# rotary-encoders.net
KiCad netlist of a schematic drawn in EAGLE
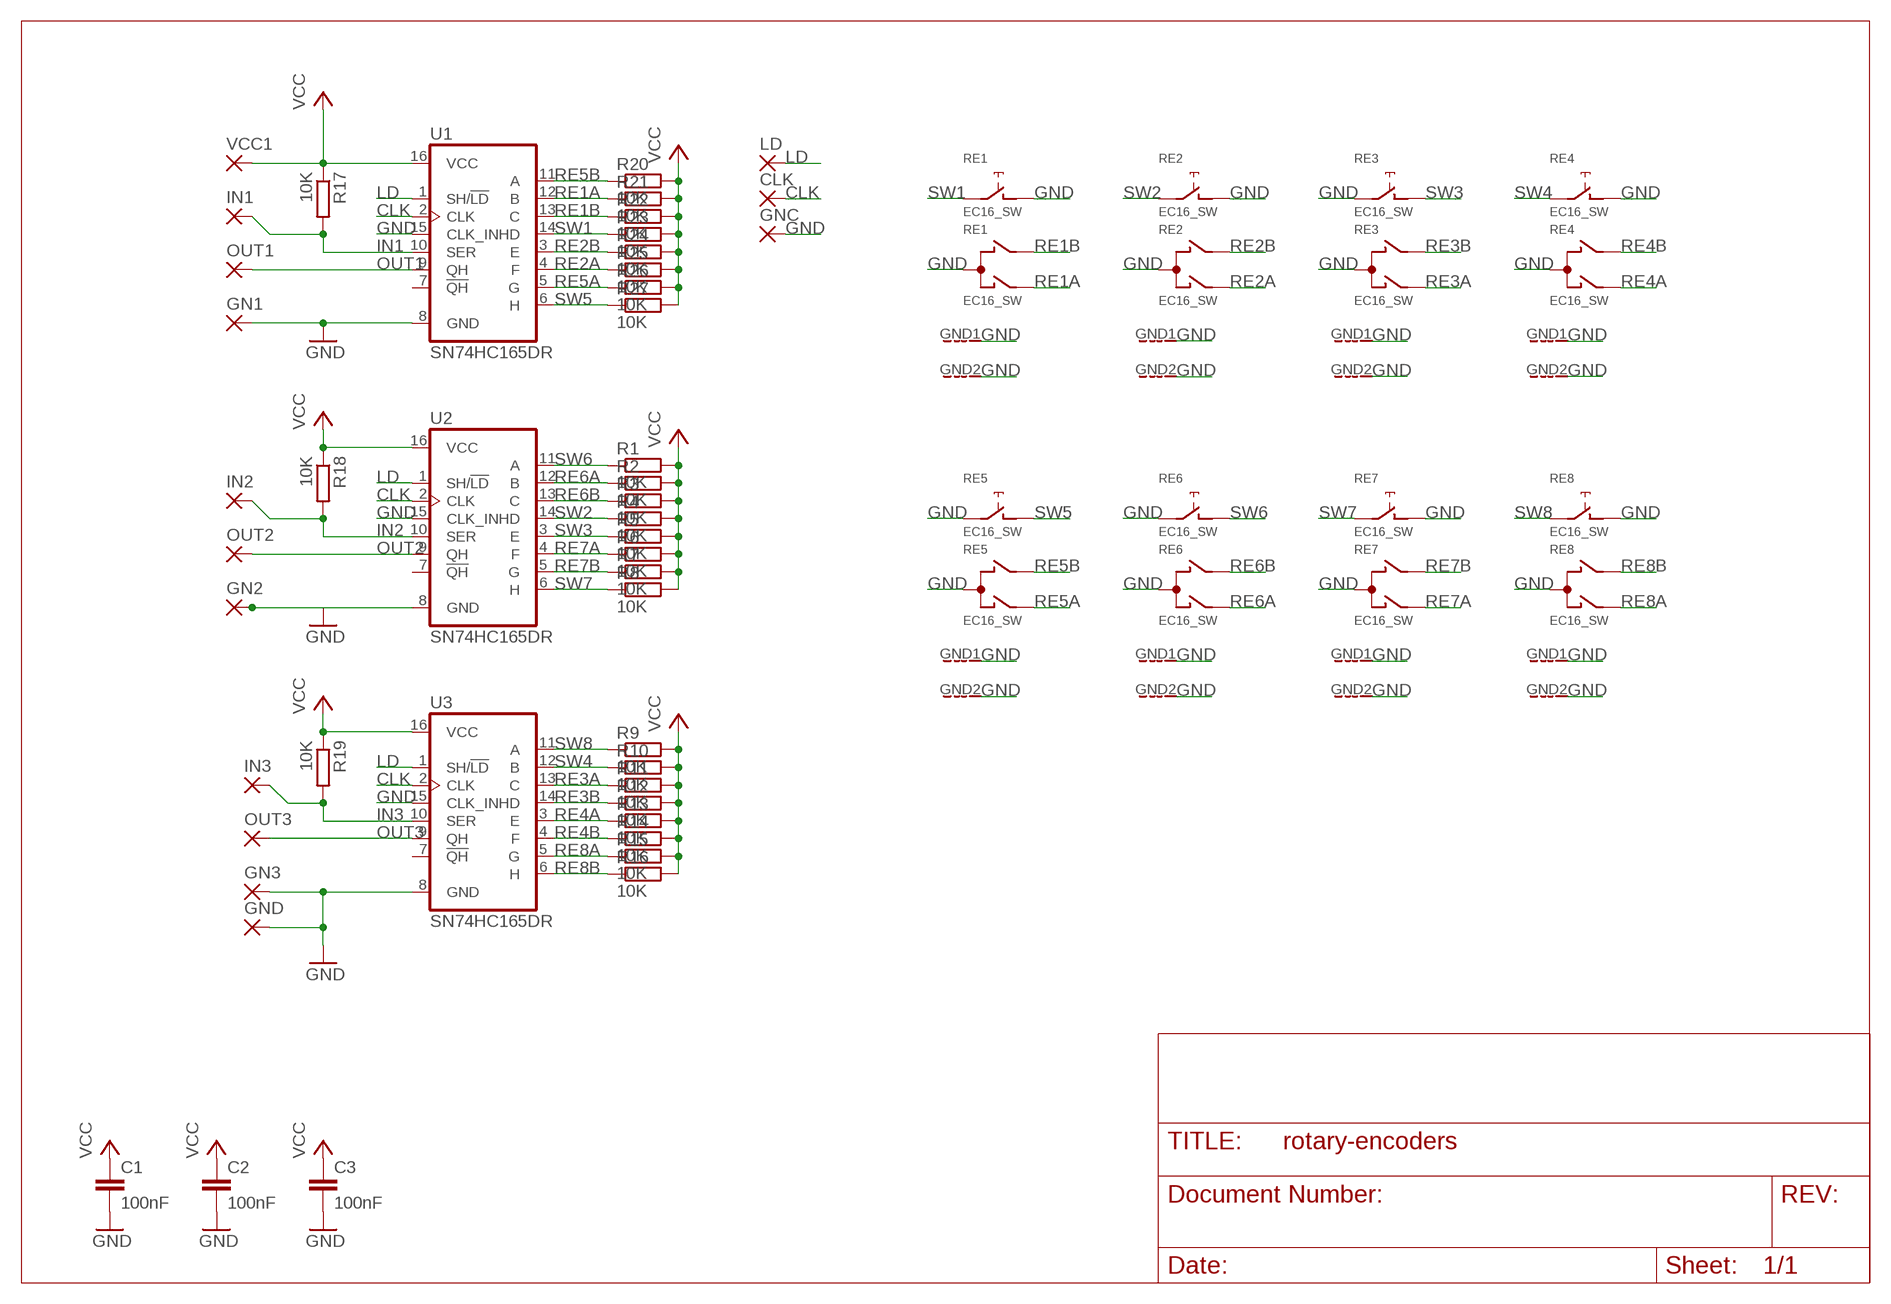
[diagram p0: schematic, sheet 1]

(export (version "E")
  (design (tool "Eeschema 10.0.6"))
  (components
    (comp (ref "C1")
      (value "100nF")
      (footprint "eagle-import:C0805")
      (libsource (lib "eagle-import") (part "C-EUC0805"))
    )
    (comp (ref "C2")
      (value "100nF")
      (footprint "eagle-import:C0805")
      (libsource (lib "eagle-import") (part "C-EUC0805"))
    )
    (comp (ref "C3")
      (value "100nF")
      (footprint "eagle-import:C0805")
      (libsource (lib "eagle-import") (part "C-EUC0805"))
    )
    (comp (ref "CLK")
      (value "1,6/0,9")
      (footprint "eagle-import:1,6_0,9")
      (libsource (lib "eagle-import") (part "1,6/0,9"))
    )
    (comp (ref "GN1")
      (value "1,6/0,9")
      (footprint "eagle-import:1,6_0,9")
      (libsource (lib "eagle-import") (part "1,6/0,9"))
    )
    (comp (ref "GN2")
      (value "1,6/0,9")
      (footprint "eagle-import:1,6_0,9")
      (libsource (lib "eagle-import") (part "1,6/0,9"))
    )
    (comp (ref "GN3")
      (value "1,6/0,9")
      (footprint "eagle-import:1,6_0,9")
      (libsource (lib "eagle-import") (part "1,6/0,9"))
    )
    (comp (ref "GNC")
      (value "1,6/0,9")
      (footprint "eagle-import:1,6_0,9")
      (libsource (lib "eagle-import") (part "1,6/0,9"))
    )
    (comp (ref "GND")
      (value "1,6/0,9")
      (footprint "eagle-import:1,6_0,9")
      (libsource (lib "eagle-import") (part "1,6/0,9"))
    )
    (comp (ref "IN1")
      (value "1,6/0,9")
      (footprint "eagle-import:1,6_0,9")
      (libsource (lib "eagle-import") (part "1,6/0,9"))
    )
    (comp (ref "IN2")
      (value "1,6/0,9")
      (footprint "eagle-import:1,6_0,9")
      (libsource (lib "eagle-import") (part "1,6/0,9"))
    )
    (comp (ref "IN3")
      (value "1,6/0,9")
      (footprint "eagle-import:1,6_0,9")
      (libsource (lib "eagle-import") (part "1,6/0,9"))
    )
    (comp (ref "LD")
      (value "1,6/0,9")
      (footprint "eagle-import:1,6_0,9")
      (libsource (lib "eagle-import") (part "1,6/0,9"))
    )
    (comp (ref "OUT1")
      (value "1,6/0,9")
      (footprint "eagle-import:1,6_0,9")
      (libsource (lib "eagle-import") (part "1,6/0,9"))
    )
    (comp (ref "OUT2")
      (value "1,6/0,9")
      (footprint "eagle-import:1,6_0,9")
      (libsource (lib "eagle-import") (part "1,6/0,9"))
    )
    (comp (ref "OUT3")
      (value "1,6/0,9")
      (footprint "eagle-import:1,6_0,9")
      (libsource (lib "eagle-import") (part "1,6/0,9"))
    )
    (comp (ref "R1")
      (value "10K")
      (footprint "eagle-import:R0805")
      (libsource (lib "eagle-import") (part "R-EU_R0805"))
    )
    (comp (ref "R2")
      (value "10K")
      (footprint "eagle-import:R0805")
      (libsource (lib "eagle-import") (part "R-EU_R0805"))
    )
    (comp (ref "R3")
      (value "10K")
      (footprint "eagle-import:R0805")
      (libsource (lib "eagle-import") (part "R-EU_R0805"))
    )
    (comp (ref "R4")
      (value "10K")
      (footprint "eagle-import:R0805")
      (libsource (lib "eagle-import") (part "R-EU_R0805"))
    )
    (comp (ref "R5")
      (value "10K")
      (footprint "eagle-import:R0805")
      (libsource (lib "eagle-import") (part "R-EU_R0805"))
    )
    (comp (ref "R6")
      (value "10K")
      (footprint "eagle-import:R0805")
      (libsource (lib "eagle-import") (part "R-EU_R0805"))
    )
    (comp (ref "R7")
      (value "10K")
      (footprint "eagle-import:R0805")
      (libsource (lib "eagle-import") (part "R-EU_R0805"))
    )
    (comp (ref "R8")
      (value "10K")
      (footprint "eagle-import:R0805")
      (libsource (lib "eagle-import") (part "R-EU_R0805"))
    )
    (comp (ref "R9")
      (value "10K")
      (footprint "eagle-import:R0805")
      (libsource (lib "eagle-import") (part "R-EU_R0805"))
    )
    (comp (ref "R10")
      (value "10K")
      (footprint "eagle-import:R0805")
      (libsource (lib "eagle-import") (part "R-EU_R0805"))
    )
    (comp (ref "R11")
      (value "10K")
      (footprint "eagle-import:R0805")
      (libsource (lib "eagle-import") (part "R-EU_R0805"))
    )
    (comp (ref "R12")
      (value "10K")
      (footprint "eagle-import:R0805")
      (libsource (lib "eagle-import") (part "R-EU_R0805"))
    )
    (comp (ref "R13")
      (value "10K")
      (footprint "eagle-import:R0805")
      (libsource (lib "eagle-import") (part "R-EU_R0805"))
    )
    (comp (ref "R14")
      (value "10K")
      (footprint "eagle-import:R0805")
      (libsource (lib "eagle-import") (part "R-EU_R0805"))
    )
    (comp (ref "R15")
      (value "10K")
      (footprint "eagle-import:R0805")
      (libsource (lib "eagle-import") (part "R-EU_R0805"))
    )
    (comp (ref "R16")
      (value "10K")
      (footprint "eagle-import:R0805")
      (libsource (lib "eagle-import") (part "R-EU_R0805"))
    )
    (comp (ref "R17")
      (value "10K")
      (footprint "eagle-import:R0805")
      (libsource (lib "eagle-import") (part "R-EU_R0805"))
    )
    (comp (ref "R18")
      (value "10K")
      (footprint "eagle-import:R0805")
      (libsource (lib "eagle-import") (part "R-EU_R0805"))
    )
    (comp (ref "R19")
      (value "10K")
      (footprint "eagle-import:R0805")
      (libsource (lib "eagle-import") (part "R-EU_R0805"))
    )
    (comp (ref "R20")
      (value "10K")
      (footprint "eagle-import:R0805")
      (libsource (lib "eagle-import") (part "R-EU_R0805"))
    )
    (comp (ref "R21")
      (value "10K")
      (footprint "eagle-import:R0805")
      (libsource (lib "eagle-import") (part "R-EU_R0805"))
    )
    (comp (ref "R22")
      (value "10K")
      (footprint "eagle-import:R0805")
      (libsource (lib "eagle-import") (part "R-EU_R0805"))
    )
    (comp (ref "R23")
      (value "10K")
      (footprint "eagle-import:R0805")
      (libsource (lib "eagle-import") (part "R-EU_R0805"))
    )
    (comp (ref "R24")
      (value "10K")
      (footprint "eagle-import:R0805")
      (libsource (lib "eagle-import") (part "R-EU_R0805"))
    )
    (comp (ref "R25")
      (value "10K")
      (footprint "eagle-import:R0805")
      (libsource (lib "eagle-import") (part "R-EU_R0805"))
    )
    (comp (ref "R26")
      (value "10K")
      (footprint "eagle-import:R0805")
      (libsource (lib "eagle-import") (part "R-EU_R0805"))
    )
    (comp (ref "R27")
      (value "10K")
      (footprint "eagle-import:R0805")
      (libsource (lib "eagle-import") (part "R-EU_R0805"))
    )
    (comp (ref "RE1")
      (value "EC16_SW")
      (footprint "eagle-import:EC16_SW")
      (libsource (lib "eagle-import") (part "EC16_SW"))
    )
    (comp (ref "RE2")
      (value "EC16_SW")
      (footprint "eagle-import:EC16_SW")
      (libsource (lib "eagle-import") (part "EC16_SW"))
    )
    (comp (ref "RE3")
      (value "EC16_SW")
      (footprint "eagle-import:EC16_SW")
      (libsource (lib "eagle-import") (part "EC16_SW"))
    )
    (comp (ref "RE4")
      (value "EC16_SW")
      (footprint "eagle-import:EC16_SW")
      (libsource (lib "eagle-import") (part "EC16_SW"))
    )
    (comp (ref "RE5")
      (value "EC16_SW")
      (footprint "eagle-import:EC16_SW")
      (libsource (lib "eagle-import") (part "EC16_SW"))
    )
    (comp (ref "RE6")
      (value "EC16_SW")
      (footprint "eagle-import:EC16_SW")
      (libsource (lib "eagle-import") (part "EC16_SW"))
    )
    (comp (ref "RE7")
      (value "EC16_SW")
      (footprint "eagle-import:EC16_SW")
      (libsource (lib "eagle-import") (part "EC16_SW"))
    )
    (comp (ref "RE8")
      (value "EC16_SW")
      (footprint "eagle-import:EC16_SW")
      (libsource (lib "eagle-import") (part "EC16_SW"))
    )
    (comp (ref "U1")
      (value "SN74HC165DR")
      (footprint "eagle-import:SO16")
      (libsource (lib "eagle-import") (part "74165DHC"))
    )
    (comp (ref "U2")
      (value "SN74HC165DR")
      (footprint "eagle-import:SO16")
      (libsource (lib "eagle-import") (part "74165DHC"))
    )
    (comp (ref "U3")
      (value "SN74HC165DR")
      (footprint "eagle-import:SO16")
      (libsource (lib "eagle-import") (part "74165DHC"))
    )
    (comp (ref "VCC1")
      (value "1,6/0,9")
      (footprint "eagle-import:1,6_0,9")
      (libsource (lib "eagle-import") (part "1,6/0,9"))
    )
  )
  (nets
    (net (code "1") (name "/CLK") (class "Default")
      (node (ref "CLK") (pin "1") (pinfunction "P_1") (pintype "passive"))
      (node (ref "U1") (pin "2") (pinfunction "CLK_2") (pintype "input"))
      (node (ref "U2") (pin "2") (pinfunction "CLK_2") (pintype "input"))
      (node (ref "U3") (pin "2") (pinfunction "CLK_2") (pintype "input"))
    )
    (net (code "2") (name "/IN1") (class "Default")
      (node (ref "IN1") (pin "1") (pinfunction "P_1") (pintype "passive"))
      (node (ref "R17") (pin "2") (pinfunction "2_2") (pintype "passive"))
      (node (ref "U1") (pin "10") (pinfunction "SER_10") (pintype "input"))
    )
    (net (code "3") (name "/IN2") (class "Default")
      (node (ref "IN2") (pin "1") (pinfunction "P_1") (pintype "passive"))
      (node (ref "R18") (pin "2") (pinfunction "2_2") (pintype "passive"))
      (node (ref "U2") (pin "10") (pinfunction "SER_10") (pintype "input"))
    )
    (net (code "4") (name "/IN3") (class "Default")
      (node (ref "IN3") (pin "1") (pinfunction "P_1") (pintype "passive"))
      (node (ref "R19") (pin "2") (pinfunction "2_2") (pintype "passive"))
      (node (ref "U3") (pin "10") (pinfunction "SER_10") (pintype "input"))
    )
    (net (code "5") (name "/LD") (class "Default")
      (node (ref "LD") (pin "1") (pinfunction "P_1") (pintype "passive"))
      (node (ref "U1") (pin "1") (pinfunction "SH/~{LD}_1") (pintype "input"))
      (node (ref "U2") (pin "1") (pinfunction "SH/~{LD}_1") (pintype "input"))
      (node (ref "U3") (pin "1") (pinfunction "SH/~{LD}_1") (pintype "input"))
    )
    (net (code "6") (name "/OUT1") (class "Default")
      (node (ref "OUT1") (pin "1") (pinfunction "P_1") (pintype "passive"))
      (node (ref "U1") (pin "9") (pinfunction "QH_9") (pintype "tri_state"))
    )
    (net (code "7") (name "/OUT2") (class "Default")
      (node (ref "OUT2") (pin "1") (pinfunction "P_1") (pintype "passive"))
      (node (ref "U2") (pin "9") (pinfunction "QH_9") (pintype "tri_state"))
    )
    (net (code "8") (name "/OUT3") (class "Default")
      (node (ref "OUT3") (pin "1") (pinfunction "P_1") (pintype "passive"))
      (node (ref "U3") (pin "9") (pinfunction "QH_9") (pintype "tri_state"))
    )
    (net (code "9") (name "/RE1A") (class "Default")
      (node (ref "R21") (pin "1") (pinfunction "1_1") (pintype "passive"))
      (node (ref "RE1") (pin "A") (pinfunction "A_A") (pintype "passive"))
      (node (ref "U1") (pin "12") (pinfunction "B_12") (pintype "tri_state"))
    )
    (net (code "10") (name "/RE1B") (class "Default")
      (node (ref "R22") (pin "1") (pinfunction "1_1") (pintype "passive"))
      (node (ref "RE1") (pin "B") (pinfunction "B_B") (pintype "passive"))
      (node (ref "U1") (pin "13") (pinfunction "C_13") (pintype "tri_state"))
    )
    (net (code "11") (name "/RE2A") (class "Default")
      (node (ref "R25") (pin "1") (pinfunction "1_1") (pintype "passive"))
      (node (ref "RE2") (pin "A") (pinfunction "A_A") (pintype "passive"))
      (node (ref "U1") (pin "4") (pinfunction "F_4") (pintype "tri_state"))
    )
    (net (code "12") (name "/RE2B") (class "Default")
      (node (ref "R24") (pin "1") (pinfunction "1_1") (pintype "passive"))
      (node (ref "RE2") (pin "B") (pinfunction "B_B") (pintype "passive"))
      (node (ref "U1") (pin "3") (pinfunction "E_3") (pintype "tri_state"))
    )
    (net (code "13") (name "/RE3A") (class "Default")
      (node (ref "R11") (pin "1") (pinfunction "1_1") (pintype "passive"))
      (node (ref "RE3") (pin "A") (pinfunction "A_A") (pintype "passive"))
      (node (ref "U3") (pin "13") (pinfunction "C_13") (pintype "tri_state"))
    )
    (net (code "14") (name "/RE3B") (class "Default")
      (node (ref "R12") (pin "1") (pinfunction "1_1") (pintype "passive"))
      (node (ref "RE3") (pin "B") (pinfunction "B_B") (pintype "passive"))
      (node (ref "U3") (pin "14") (pinfunction "D_14") (pintype "tri_state"))
    )
    (net (code "15") (name "/RE4A") (class "Default")
      (node (ref "R13") (pin "1") (pinfunction "1_1") (pintype "passive"))
      (node (ref "RE4") (pin "A") (pinfunction "A_A") (pintype "passive"))
      (node (ref "U3") (pin "3") (pinfunction "E_3") (pintype "tri_state"))
    )
    (net (code "16") (name "/RE4B") (class "Default")
      (node (ref "R14") (pin "1") (pinfunction "1_1") (pintype "passive"))
      (node (ref "RE4") (pin "B") (pinfunction "B_B") (pintype "passive"))
      (node (ref "U3") (pin "4") (pinfunction "F_4") (pintype "tri_state"))
    )
    (net (code "17") (name "/RE5A") (class "Default")
      (node (ref "R26") (pin "1") (pinfunction "1_1") (pintype "passive"))
      (node (ref "RE5") (pin "A") (pinfunction "A_A") (pintype "passive"))
      (node (ref "U1") (pin "5") (pinfunction "G_5") (pintype "tri_state"))
    )
    (net (code "18") (name "/RE5B") (class "Default")
      (node (ref "R20") (pin "1") (pinfunction "1_1") (pintype "passive"))
      (node (ref "RE5") (pin "B") (pinfunction "B_B") (pintype "passive"))
      (node (ref "U1") (pin "11") (pinfunction "A_11") (pintype "tri_state"))
    )
    (net (code "19") (name "/RE6A") (class "Default")
      (node (ref "R2") (pin "1") (pinfunction "1_1") (pintype "passive"))
      (node (ref "RE6") (pin "A") (pinfunction "A_A") (pintype "passive"))
      (node (ref "U2") (pin "12") (pinfunction "B_12") (pintype "tri_state"))
    )
    (net (code "20") (name "/RE6B") (class "Default")
      (node (ref "R3") (pin "1") (pinfunction "1_1") (pintype "passive"))
      (node (ref "RE6") (pin "B") (pinfunction "B_B") (pintype "passive"))
      (node (ref "U2") (pin "13") (pinfunction "C_13") (pintype "tri_state"))
    )
    (net (code "21") (name "/RE7A") (class "Default")
      (node (ref "R6") (pin "1") (pinfunction "1_1") (pintype "passive"))
      (node (ref "RE7") (pin "A") (pinfunction "A_A") (pintype "passive"))
      (node (ref "U2") (pin "4") (pinfunction "F_4") (pintype "tri_state"))
    )
    (net (code "22") (name "/RE7B") (class "Default")
      (node (ref "R7") (pin "1") (pinfunction "1_1") (pintype "passive"))
      (node (ref "RE7") (pin "B") (pinfunction "B_B") (pintype "passive"))
      (node (ref "U2") (pin "5") (pinfunction "G_5") (pintype "tri_state"))
    )
    (net (code "23") (name "/RE8A") (class "Default")
      (node (ref "R15") (pin "1") (pinfunction "1_1") (pintype "passive"))
      (node (ref "RE8") (pin "A") (pinfunction "A_A") (pintype "passive"))
      (node (ref "U3") (pin "5") (pinfunction "G_5") (pintype "tri_state"))
    )
    (net (code "24") (name "/RE8B") (class "Default")
      (node (ref "R16") (pin "1") (pinfunction "1_1") (pintype "passive"))
      (node (ref "RE8") (pin "B") (pinfunction "B_B") (pintype "passive"))
      (node (ref "U3") (pin "6") (pinfunction "H_6") (pintype "tri_state"))
    )
    (net (code "25") (name "/SW1") (class "Default")
      (node (ref "R23") (pin "1") (pinfunction "1_1") (pintype "passive"))
      (node (ref "RE1") (pin "E") (pinfunction "2_E") (pintype "passive"))
      (node (ref "U1") (pin "14") (pinfunction "D_14") (pintype "tri_state"))
    )
    (net (code "26") (name "/SW2") (class "Default")
      (node (ref "R4") (pin "1") (pinfunction "1_1") (pintype "passive"))
      (node (ref "RE2") (pin "E") (pinfunction "2_E") (pintype "passive"))
      (node (ref "U2") (pin "14") (pinfunction "D_14") (pintype "tri_state"))
    )
    (net (code "27") (name "/SW3") (class "Default")
      (node (ref "R5") (pin "1") (pinfunction "1_1") (pintype "passive"))
      (node (ref "RE3") (pin "D") (pinfunction "1_D") (pintype "passive"))
      (node (ref "U2") (pin "3") (pinfunction "E_3") (pintype "tri_state"))
    )
    (net (code "28") (name "/SW4") (class "Default")
      (node (ref "R10") (pin "1") (pinfunction "1_1") (pintype "passive"))
      (node (ref "RE4") (pin "E") (pinfunction "2_E") (pintype "passive"))
      (node (ref "U3") (pin "12") (pinfunction "B_12") (pintype "tri_state"))
    )
    (net (code "29") (name "/SW5") (class "Default")
      (node (ref "R27") (pin "1") (pinfunction "1_1") (pintype "passive"))
      (node (ref "RE5") (pin "D") (pinfunction "1_D") (pintype "passive"))
      (node (ref "U1") (pin "6") (pinfunction "H_6") (pintype "tri_state"))
    )
    (net (code "30") (name "/SW6") (class "Default")
      (node (ref "R1") (pin "1") (pinfunction "1_1") (pintype "passive"))
      (node (ref "RE6") (pin "D") (pinfunction "1_D") (pintype "passive"))
      (node (ref "U2") (pin "11") (pinfunction "A_11") (pintype "tri_state"))
    )
    (net (code "31") (name "/SW7") (class "Default")
      (node (ref "R8") (pin "1") (pinfunction "1_1") (pintype "passive"))
      (node (ref "RE7") (pin "E") (pinfunction "2_E") (pintype "passive"))
      (node (ref "U2") (pin "6") (pinfunction "H_6") (pintype "tri_state"))
    )
    (net (code "32") (name "/SW8") (class "Default")
      (node (ref "R9") (pin "1") (pinfunction "1_1") (pintype "passive"))
      (node (ref "RE8") (pin "E") (pinfunction "2_E") (pintype "passive"))
      (node (ref "U3") (pin "11") (pinfunction "A_11") (pintype "tri_state"))
    )
    (net (code "33") (name "GND") (class "Default")
      (node (ref "C1") (pin "2") (pinfunction "2_2") (pintype "passive"))
      (node (ref "C2") (pin "2") (pinfunction "2_2") (pintype "passive"))
      (node (ref "C3") (pin "2") (pinfunction "2_2") (pintype "passive"))
      (node (ref "GN1") (pin "1") (pinfunction "P_1") (pintype "passive"))
      (node (ref "GN2") (pin "1") (pinfunction "P_1") (pintype "passive"))
      (node (ref "GN3") (pin "1") (pinfunction "P_1") (pintype "passive"))
      (node (ref "GNC") (pin "1") (pinfunction "P_1") (pintype "passive"))
      (node (ref "GND") (pin "1") (pinfunction "P_1") (pintype "passive"))
      (node (ref "RE1") (pin "C") (pinfunction "C_C") (pintype "passive"))
      (node (ref "RE1") (pin "D") (pinfunction "1_D") (pintype "passive"))
      (node (ref "RE1") (pin "GND1") (pinfunction "G_GND1") (pintype "passive"))
      (node (ref "RE1") (pin "GND2") (pinfunction "G_GND2") (pintype "passive"))
      (node (ref "RE2") (pin "C") (pinfunction "C_C") (pintype "passive"))
      (node (ref "RE2") (pin "D") (pinfunction "1_D") (pintype "passive"))
      (node (ref "RE2") (pin "GND1") (pinfunction "G_GND1") (pintype "passive"))
      (node (ref "RE2") (pin "GND2") (pinfunction "G_GND2") (pintype "passive"))
      (node (ref "RE3") (pin "C") (pinfunction "C_C") (pintype "passive"))
      (node (ref "RE3") (pin "E") (pinfunction "2_E") (pintype "passive"))
      (node (ref "RE3") (pin "GND1") (pinfunction "G_GND1") (pintype "passive"))
      (node (ref "RE3") (pin "GND2") (pinfunction "G_GND2") (pintype "passive"))
      (node (ref "RE4") (pin "C") (pinfunction "C_C") (pintype "passive"))
      (node (ref "RE4") (pin "D") (pinfunction "1_D") (pintype "passive"))
      (node (ref "RE4") (pin "GND1") (pinfunction "G_GND1") (pintype "passive"))
      (node (ref "RE4") (pin "GND2") (pinfunction "G_GND2") (pintype "passive"))
      (node (ref "RE5") (pin "C") (pinfunction "C_C") (pintype "passive"))
      (node (ref "RE5") (pin "E") (pinfunction "2_E") (pintype "passive"))
      (node (ref "RE5") (pin "GND1") (pinfunction "G_GND1") (pintype "passive"))
      (node (ref "RE5") (pin "GND2") (pinfunction "G_GND2") (pintype "passive"))
      (node (ref "RE6") (pin "C") (pinfunction "C_C") (pintype "passive"))
      (node (ref "RE6") (pin "E") (pinfunction "2_E") (pintype "passive"))
      (node (ref "RE6") (pin "GND1") (pinfunction "G_GND1") (pintype "passive"))
      (node (ref "RE6") (pin "GND2") (pinfunction "G_GND2") (pintype "passive"))
      (node (ref "RE7") (pin "C") (pinfunction "C_C") (pintype "passive"))
      (node (ref "RE7") (pin "D") (pinfunction "1_D") (pintype "passive"))
      (node (ref "RE7") (pin "GND1") (pinfunction "G_GND1") (pintype "passive"))
      (node (ref "RE7") (pin "GND2") (pinfunction "G_GND2") (pintype "passive"))
      (node (ref "RE8") (pin "C") (pinfunction "C_C") (pintype "passive"))
      (node (ref "RE8") (pin "D") (pinfunction "1_D") (pintype "passive"))
      (node (ref "RE8") (pin "GND1") (pinfunction "G_GND1") (pintype "passive"))
      (node (ref "RE8") (pin "GND2") (pinfunction "G_GND2") (pintype "passive"))
      (node (ref "U1") (pin "15") (pinfunction "CLK_INH_15") (pintype "input"))
      (node (ref "U1") (pin "8") (pinfunction "GND_8") (pintype "power_in"))
      (node (ref "U2") (pin "15") (pinfunction "CLK_INH_15") (pintype "input"))
      (node (ref "U2") (pin "8") (pinfunction "GND_8") (pintype "power_in"))
      (node (ref "U3") (pin "15") (pinfunction "CLK_INH_15") (pintype "input"))
      (node (ref "U3") (pin "8") (pinfunction "GND_8") (pintype "power_in"))
    )
    (net (code "34") (name "VCC") (class "Default")
      (node (ref "C1") (pin "1") (pinfunction "1_1") (pintype "passive"))
      (node (ref "C2") (pin "1") (pinfunction "1_1") (pintype "passive"))
      (node (ref "C3") (pin "1") (pinfunction "1_1") (pintype "passive"))
      (node (ref "R1") (pin "2") (pinfunction "2_2") (pintype "passive"))
      (node (ref "R10") (pin "2") (pinfunction "2_2") (pintype "passive"))
      (node (ref "R11") (pin "2") (pinfunction "2_2") (pintype "passive"))
      (node (ref "R12") (pin "2") (pinfunction "2_2") (pintype "passive"))
      (node (ref "R13") (pin "2") (pinfunction "2_2") (pintype "passive"))
      (node (ref "R14") (pin "2") (pinfunction "2_2") (pintype "passive"))
      (node (ref "R15") (pin "2") (pinfunction "2_2") (pintype "passive"))
      (node (ref "R16") (pin "2") (pinfunction "2_2") (pintype "passive"))
      (node (ref "R17") (pin "1") (pinfunction "1_1") (pintype "passive"))
      (node (ref "R18") (pin "1") (pinfunction "1_1") (pintype "passive"))
      (node (ref "R19") (pin "1") (pinfunction "1_1") (pintype "passive"))
      (node (ref "R2") (pin "2") (pinfunction "2_2") (pintype "passive"))
      (node (ref "R20") (pin "2") (pinfunction "2_2") (pintype "passive"))
      (node (ref "R21") (pin "2") (pinfunction "2_2") (pintype "passive"))
      (node (ref "R22") (pin "2") (pinfunction "2_2") (pintype "passive"))
      (node (ref "R23") (pin "2") (pinfunction "2_2") (pintype "passive"))
      (node (ref "R24") (pin "2") (pinfunction "2_2") (pintype "passive"))
      (node (ref "R25") (pin "2") (pinfunction "2_2") (pintype "passive"))
      (node (ref "R26") (pin "2") (pinfunction "2_2") (pintype "passive"))
      (node (ref "R27") (pin "2") (pinfunction "2_2") (pintype "passive"))
      (node (ref "R3") (pin "2") (pinfunction "2_2") (pintype "passive"))
      (node (ref "R4") (pin "2") (pinfunction "2_2") (pintype "passive"))
      (node (ref "R5") (pin "2") (pinfunction "2_2") (pintype "passive"))
      (node (ref "R6") (pin "2") (pinfunction "2_2") (pintype "passive"))
      (node (ref "R7") (pin "2") (pinfunction "2_2") (pintype "passive"))
      (node (ref "R8") (pin "2") (pinfunction "2_2") (pintype "passive"))
      (node (ref "R9") (pin "2") (pinfunction "2_2") (pintype "passive"))
      (node (ref "U1") (pin "16") (pinfunction "VCC_16") (pintype "power_in"))
      (node (ref "U2") (pin "16") (pinfunction "VCC_16") (pintype "power_in"))
      (node (ref "U3") (pin "16") (pinfunction "VCC_16") (pintype "power_in"))
      (node (ref "VCC1") (pin "1") (pinfunction "P_1") (pintype "passive"))
    )
    (net (code "35") (name "unconnected-(U1-~{QH}-Pad7)") (class "Default")
      (node (ref "U1") (pin "7") (pinfunction "~{QH}_7") (pintype "input"))
    )
    (net (code "36") (name "unconnected-(U2-~{QH}-Pad7)") (class "Default")
      (node (ref "U2") (pin "7") (pinfunction "~{QH}_7") (pintype "input"))
    )
    (net (code "37") (name "unconnected-(U3-~{QH}-Pad7)") (class "Default")
      (node (ref "U3") (pin "7") (pinfunction "~{QH}_7") (pintype "input"))
    )
  )
)
